# Version_1_3.net
KiCad netlist of a schematic drawn in EAGLE
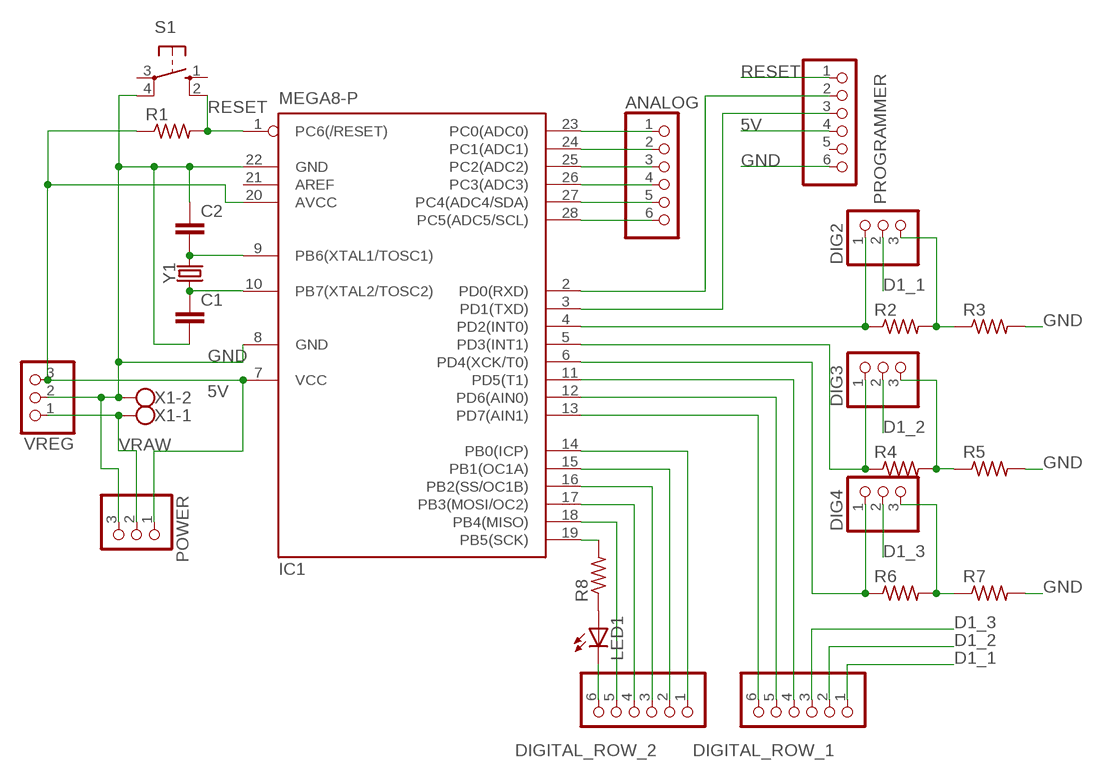
[diagram p0: schematic, sheet 1]

(export (version "E")
  (design (tool "Eeschema 10.0.6"))
  (components
    (comp (ref "ANALOG")
      (value "PINHD-1X6B")
      (footprint "eagle-import:1X06-BIG")
      (libsource (lib "eagle-import") (part "PINHD-1X6B"))
    )
    (comp (ref "C1")
      (value "C2,5-3")
      (footprint "eagle-import:C2.5-3")
      (libsource (lib "eagle-import") (part "C2,5-3"))
    )
    (comp (ref "C2")
      (value "C2,5-3")
      (footprint "eagle-import:C2.5-3")
      (libsource (lib "eagle-import") (part "C2,5-3"))
    )
    (comp (ref "DIG2")
      (value "PINHD-1X3")
      (footprint "eagle-import:1X03")
      (libsource (lib "eagle-import") (part "PINHD-1X3"))
    )
    (comp (ref "DIG3")
      (value "PINHD-1X3")
      (footprint "eagle-import:1X03")
      (libsource (lib "eagle-import") (part "PINHD-1X3"))
    )
    (comp (ref "DIG4")
      (value "PINHD-1X3")
      (footprint "eagle-import:1X03")
      (libsource (lib "eagle-import") (part "PINHD-1X3"))
    )
    (comp (ref "DIGITAL_ROW_1")
      (value "PINHD-1X6B")
      (footprint "eagle-import:1X06-BIG")
      (libsource (lib "eagle-import") (part "PINHD-1X6B"))
    )
    (comp (ref "DIGITAL_ROW_2")
      (value "PINHD-1X6B")
      (footprint "eagle-import:1X06-BIG")
      (libsource (lib "eagle-import") (part "PINHD-1X6B"))
    )
    (comp (ref "IC1")
      (value "MEGA8-P")
      (footprint "eagle-import:DIL28-3")
      (libsource (lib "eagle-import") (part "MEGA8-P"))
    )
    (comp (ref "LED1")
      (value "LED3MM")
      (footprint "eagle-import:LED3MM")
      (libsource (lib "eagle-import") (part "LED3MM"))
    )
    (comp (ref "POWER")
      (value "PINHD-1X3")
      (footprint "eagle-import:1X03")
      (libsource (lib "eagle-import") (part "PINHD-1X3"))
    )
    (comp (ref "PROGRAMMER")
      (value "PINHD-1X6B")
      (footprint "eagle-import:1X06-BIG")
      (libsource (lib "eagle-import") (part "PINHD-1X6B"))
    )
    (comp (ref "R1")
      (value "R-US_0204/7")
      (footprint "eagle-import:0204_7")
      (libsource (lib "eagle-import") (part "R-US_0204/7"))
    )
    (comp (ref "R2")
      (value "R-US_0204/7")
      (footprint "eagle-import:0204_7")
      (libsource (lib "eagle-import") (part "R-US_0204/7"))
    )
    (comp (ref "R3")
      (value "R-US_0204/7")
      (footprint "eagle-import:0204_7")
      (libsource (lib "eagle-import") (part "R-US_0204/7"))
    )
    (comp (ref "R4")
      (value "R-US_0204/7")
      (footprint "eagle-import:0204_7")
      (libsource (lib "eagle-import") (part "R-US_0204/7"))
    )
    (comp (ref "R5")
      (value "R-US_0204/7")
      (footprint "eagle-import:0204_7")
      (libsource (lib "eagle-import") (part "R-US_0204/7"))
    )
    (comp (ref "R6")
      (value "R-US_0204/7")
      (footprint "eagle-import:0204_7")
      (libsource (lib "eagle-import") (part "R-US_0204/7"))
    )
    (comp (ref "R7")
      (value "R-US_0204/7")
      (footprint "eagle-import:0204_7")
      (libsource (lib "eagle-import") (part "R-US_0204/7"))
    )
    (comp (ref "R8")
      (value "R-US_0204/7")
      (footprint "eagle-import:0204_7")
      (libsource (lib "eagle-import") (part "R-US_0204/7"))
    )
    (comp (ref "S1")
      (value "10-XX")
      (footprint "eagle-import:B3F-10XX")
      (fields (field (name "MPN") "B3F-1000"))
      (libsource (lib "eagle-import") (part "10-XX"))
    )
    (comp (ref "VREG")
      (value "PINHD-1X3CB")
      (footprint "eagle-import:1X03-CLEANBIG")
      (libsource (lib "eagle-import") (part "PINHD-1X3CB"))
    )
    (comp (ref "X1")
      (value "W237-102")
      (footprint "eagle-import:W237-102")
      (fields (field (name "MPN") "237-102"))
      (libsource (lib "eagle-import") (part "W237-102"))
    )
    (comp (ref "Y1")
      (value "CRYSTALPTH-HC49US")
      (footprint "eagle-import:HC49US")
      (libsource (lib "eagle-import") (part "CRYSTALPTH-HC49US"))
    )
  )
  (nets
    (net (code "1") (name "/5V") (class "Default")
      (node (ref "IC1") (pin "20") (pinfunction "AVCC_20") (pintype "power_in"))
      (node (ref "IC1") (pin "7") (pinfunction "VCC_7") (pintype "power_in"))
      (node (ref "POWER") (pin "1") (pinfunction "1_1") (pintype "passive"))
      (node (ref "PROGRAMMER") (pin "4") (pinfunction "4_4") (pintype "passive"))
      (node (ref "R1") (pin "1") (pinfunction "1_1") (pintype "passive"))
      (node (ref "VREG") (pin "3") (pinfunction "3_3") (pintype "passive"))
    )
    (net (code "2") (name "/D1_1") (class "Default")
      (node (ref "DIG2") (pin "2") (pinfunction "2_2") (pintype "passive"))
      (node (ref "DIGITAL_ROW_1") (pin "1") (pinfunction "1_1") (pintype "passive"))
    )
    (net (code "3") (name "/D1_2") (class "Default")
      (node (ref "DIG3") (pin "2") (pinfunction "2_2") (pintype "passive"))
      (node (ref "DIGITAL_ROW_1") (pin "2") (pinfunction "2_2") (pintype "passive"))
    )
    (net (code "4") (name "/D1_3") (class "Default")
      (node (ref "DIG4") (pin "2") (pinfunction "2_2") (pintype "passive"))
      (node (ref "DIGITAL_ROW_1") (pin "3") (pinfunction "3_3") (pintype "passive"))
    )
    (net (code "5") (name "/GND") (class "Default")
      (node (ref "C1") (pin "2") (pinfunction "2_2") (pintype "passive"))
      (node (ref "C2") (pin "1") (pinfunction "1_1") (pintype "passive"))
      (node (ref "IC1") (pin "22") (pinfunction "GND_22") (pintype "power_in"))
      (node (ref "IC1") (pin "8") (pinfunction "GND_8") (pintype "power_in"))
      (node (ref "POWER") (pin "3") (pinfunction "3_3") (pintype "passive"))
      (node (ref "PROGRAMMER") (pin "6") (pinfunction "6_6") (pintype "passive"))
      (node (ref "R3") (pin "2") (pinfunction "2_2") (pintype "passive"))
      (node (ref "R5") (pin "2") (pinfunction "2_2") (pintype "passive"))
      (node (ref "R7") (pin "2") (pinfunction "2_2") (pintype "passive"))
      (node (ref "S1") (pin "4") (pinfunction "P1_4") (pintype "passive"))
      (node (ref "VREG") (pin "2") (pinfunction "2_2") (pintype "passive"))
      (node (ref "X1") (pin "2") (pinfunction "KL_2") (pintype "passive"))
    )
    (net (code "6") (name "/RESET") (class "Default")
      (node (ref "IC1") (pin "1") (pinfunction "PC6(/RESET)_1") (pintype "bidirectional"))
      (node (ref "PROGRAMMER") (pin "1") (pinfunction "1_1") (pintype "passive"))
      (node (ref "R1") (pin "2") (pinfunction "2_2") (pintype "passive"))
      (node (ref "S1") (pin "2") (pinfunction "S1_2") (pintype "passive"))
    )
    (net (code "7") (name "/VRAW") (class "Default")
      (node (ref "POWER") (pin "2") (pinfunction "2_2") (pintype "passive"))
      (node (ref "VREG") (pin "1") (pinfunction "1_1") (pintype "passive"))
      (node (ref "X1") (pin "1") (pinfunction "KL_1") (pintype "passive"))
    )
    (net (code "8") (name "Net-(DIG2-Pad3)") (class "Default")
      (node (ref "DIG2") (pin "3") (pinfunction "3_3") (pintype "passive"))
      (node (ref "R2") (pin "2") (pinfunction "2_2") (pintype "passive"))
      (node (ref "R3") (pin "1") (pinfunction "1_1") (pintype "passive"))
    )
    (net (code "9") (name "Net-(DIG3-Pad3)") (class "Default")
      (node (ref "DIG3") (pin "3") (pinfunction "3_3") (pintype "passive"))
      (node (ref "R4") (pin "2") (pinfunction "2_2") (pintype "passive"))
      (node (ref "R5") (pin "1") (pinfunction "1_1") (pintype "passive"))
    )
    (net (code "10") (name "Net-(DIG4-Pad3)") (class "Default")
      (node (ref "DIG4") (pin "3") (pinfunction "3_3") (pintype "passive"))
      (node (ref "R6") (pin "2") (pinfunction "2_2") (pintype "passive"))
      (node (ref "R7") (pin "1") (pinfunction "1_1") (pintype "passive"))
    )
    (net (code "11") (name "Net-(IC1-PB0(ICP))") (class "Default")
      (node (ref "DIGITAL_ROW_2") (pin "1") (pinfunction "1_1") (pintype "passive"))
      (node (ref "IC1") (pin "14") (pinfunction "PB0(ICP)_14") (pintype "bidirectional"))
    )
    (net (code "12") (name "Net-(IC1-PB1(OC1A))") (class "Default")
      (node (ref "DIGITAL_ROW_2") (pin "2") (pinfunction "2_2") (pintype "passive"))
      (node (ref "IC1") (pin "15") (pinfunction "PB1(OC1A)_15") (pintype "bidirectional"))
    )
    (net (code "13") (name "Net-(IC1-PB2(SS{slash}OC1B))") (class "Default")
      (node (ref "DIGITAL_ROW_2") (pin "3") (pinfunction "3_3") (pintype "passive"))
      (node (ref "IC1") (pin "16") (pinfunction "PB2(SS/OC1B)_16") (pintype "bidirectional"))
    )
    (net (code "14") (name "Net-(IC1-PB3(MOSI{slash}OC2))") (class "Default")
      (node (ref "DIGITAL_ROW_2") (pin "4") (pinfunction "4_4") (pintype "passive"))
      (node (ref "IC1") (pin "17") (pinfunction "PB3(MOSI/OC2)_17") (pintype "bidirectional"))
    )
    (net (code "15") (name "Net-(IC1-PB4(MISO))") (class "Default")
      (node (ref "DIGITAL_ROW_2") (pin "5") (pinfunction "5_5") (pintype "passive"))
      (node (ref "IC1") (pin "18") (pinfunction "PB4(MISO)_18") (pintype "bidirectional"))
    )
    (net (code "16") (name "Net-(IC1-PB5(SCK))") (class "Default")
      (node (ref "IC1") (pin "19") (pinfunction "PB5(SCK)_19") (pintype "bidirectional"))
      (node (ref "R8") (pin "2") (pinfunction "2_2") (pintype "passive"))
    )
    (net (code "17") (name "Net-(IC1-PB6(XTAL1{slash}TOSC1))") (class "Default")
      (node (ref "C2") (pin "2") (pinfunction "2_2") (pintype "passive"))
      (node (ref "IC1") (pin "9") (pinfunction "PB6(XTAL1/TOSC1)_9") (pintype "bidirectional"))
      (node (ref "Y1") (pin "2") (pinfunction "2_2") (pintype "passive"))
    )
    (net (code "18") (name "Net-(IC1-PB7(XTAL2{slash}TOSC2))") (class "Default")
      (node (ref "C1") (pin "1") (pinfunction "1_1") (pintype "passive"))
      (node (ref "IC1") (pin "10") (pinfunction "PB7(XTAL2/TOSC2)_10") (pintype "bidirectional"))
      (node (ref "Y1") (pin "1") (pinfunction "1_1") (pintype "passive"))
    )
    (net (code "19") (name "Net-(IC1-PC0(ADC0))") (class "Default")
      (node (ref "ANALOG") (pin "1") (pinfunction "1_1") (pintype "passive"))
      (node (ref "IC1") (pin "23") (pinfunction "PC0(ADC0)_23") (pintype "bidirectional"))
    )
    (net (code "20") (name "Net-(IC1-PC1(ADC1))") (class "Default")
      (node (ref "ANALOG") (pin "2") (pinfunction "2_2") (pintype "passive"))
      (node (ref "IC1") (pin "24") (pinfunction "PC1(ADC1)_24") (pintype "bidirectional"))
    )
    (net (code "21") (name "Net-(IC1-PC2(ADC2))") (class "Default")
      (node (ref "ANALOG") (pin "3") (pinfunction "3_3") (pintype "passive"))
      (node (ref "IC1") (pin "25") (pinfunction "PC2(ADC2)_25") (pintype "bidirectional"))
    )
    (net (code "22") (name "Net-(IC1-PC3(ADC3))") (class "Default")
      (node (ref "ANALOG") (pin "4") (pinfunction "4_4") (pintype "passive"))
      (node (ref "IC1") (pin "26") (pinfunction "PC3(ADC3)_26") (pintype "bidirectional"))
    )
    (net (code "23") (name "Net-(IC1-PC4(ADC4{slash}SDA))") (class "Default")
      (node (ref "ANALOG") (pin "5") (pinfunction "5_5") (pintype "passive"))
      (node (ref "IC1") (pin "27") (pinfunction "PC4(ADC4/SDA)_27") (pintype "bidirectional"))
    )
    (net (code "24") (name "Net-(IC1-PC5(ADC5{slash}SCL))") (class "Default")
      (node (ref "ANALOG") (pin "6") (pinfunction "6_6") (pintype "passive"))
      (node (ref "IC1") (pin "28") (pinfunction "PC5(ADC5/SCL)_28") (pintype "bidirectional"))
    )
    (net (code "25") (name "Net-(IC1-PD0(RXD))") (class "Default")
      (node (ref "IC1") (pin "2") (pinfunction "PD0(RXD)_2") (pintype "bidirectional"))
      (node (ref "PROGRAMMER") (pin "2") (pinfunction "2_2") (pintype "passive"))
    )
    (net (code "26") (name "Net-(IC1-PD1(TXD))") (class "Default")
      (node (ref "IC1") (pin "3") (pinfunction "PD1(TXD)_3") (pintype "bidirectional"))
      (node (ref "PROGRAMMER") (pin "3") (pinfunction "3_3") (pintype "passive"))
    )
    (net (code "27") (name "Net-(IC1-PD2(INT0))") (class "Default")
      (node (ref "DIG2") (pin "1") (pinfunction "1_1") (pintype "passive"))
      (node (ref "IC1") (pin "4") (pinfunction "PD2(INT0)_4") (pintype "bidirectional"))
      (node (ref "R2") (pin "1") (pinfunction "1_1") (pintype "passive"))
    )
    (net (code "28") (name "Net-(IC1-PD3(INT1))") (class "Default")
      (node (ref "DIG3") (pin "1") (pinfunction "1_1") (pintype "passive"))
      (node (ref "IC1") (pin "5") (pinfunction "PD3(INT1)_5") (pintype "bidirectional"))
      (node (ref "R4") (pin "1") (pinfunction "1_1") (pintype "passive"))
    )
    (net (code "29") (name "Net-(IC1-PD4(XCK{slash}T0))") (class "Default")
      (node (ref "DIG4") (pin "1") (pinfunction "1_1") (pintype "passive"))
      (node (ref "IC1") (pin "6") (pinfunction "PD4(XCK/T0)_6") (pintype "bidirectional"))
      (node (ref "R6") (pin "1") (pinfunction "1_1") (pintype "passive"))
    )
    (net (code "30") (name "Net-(IC1-PD5(T1))") (class "Default")
      (node (ref "DIGITAL_ROW_1") (pin "4") (pinfunction "4_4") (pintype "passive"))
      (node (ref "IC1") (pin "11") (pinfunction "PD5(T1)_11") (pintype "bidirectional"))
    )
    (net (code "31") (name "Net-(IC1-PD6(AIN0))") (class "Default")
      (node (ref "DIGITAL_ROW_1") (pin "5") (pinfunction "5_5") (pintype "passive"))
      (node (ref "IC1") (pin "12") (pinfunction "PD6(AIN0)_12") (pintype "bidirectional"))
    )
    (net (code "32") (name "Net-(IC1-PD7(AIN1))") (class "Default")
      (node (ref "DIGITAL_ROW_1") (pin "6") (pinfunction "6_6") (pintype "passive"))
      (node (ref "IC1") (pin "13") (pinfunction "PD7(AIN1)_13") (pintype "bidirectional"))
    )
    (net (code "33") (name "Net-(LED1-C)") (class "Default")
      (node (ref "DIGITAL_ROW_2") (pin "6") (pinfunction "6_6") (pintype "passive"))
      (node (ref "LED1") (pin "K") (pinfunction "C_K") (pintype "passive"))
    )
    (net (code "34") (name "Net-(LED1-PadA)") (class "Default")
      (node (ref "LED1") (pin "A") (pinfunction "A_A") (pintype "passive"))
      (node (ref "R8") (pin "1") (pinfunction "1_1") (pintype "passive"))
    )
    (net (code "35") (name "unconnected-(IC1-AREF-Pad21)") (class "Default")
      (node (ref "IC1") (pin "21") (pinfunction "AREF_21") (pintype "passive"))
    )
    (net (code "36") (name "unconnected-(PROGRAMMER-Pad5)") (class "Default")
      (node (ref "PROGRAMMER") (pin "5") (pinfunction "5_5") (pintype "passive"))
    )
    (net (code "37") (name "unconnected-(S1-P-Pad3)") (class "Default")
      (node (ref "S1") (pin "3") (pinfunction "P_3") (pintype "passive"))
    )
    (net (code "38") (name "unconnected-(S1-S-Pad1)") (class "Default")
      (node (ref "S1") (pin "1") (pinfunction "S_1") (pintype "passive"))
    )
  )
)
